# Sheet2.net
KiCad netlist of a schematic drawn in Altium Designer
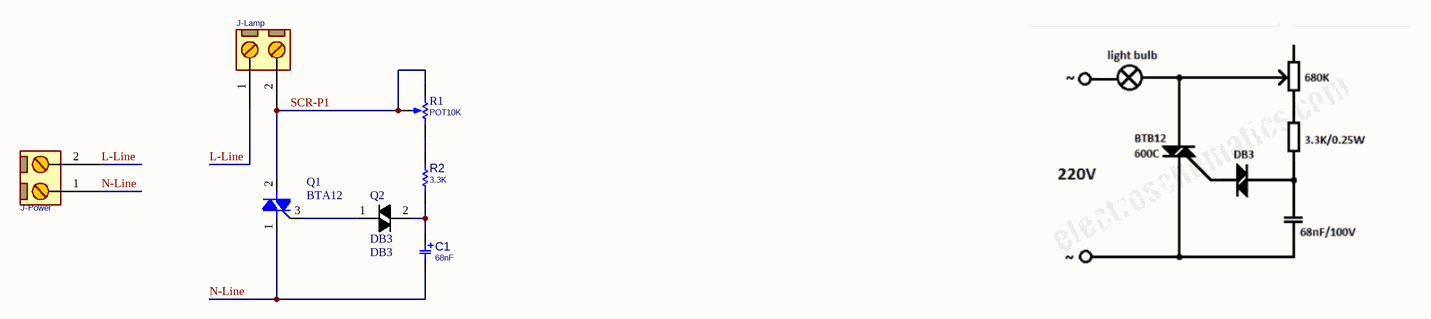
[diagram p0: Sheet2.SchDoc]

(export (version "E")
  (design (tool "Eeschema 10.0.6"))
  (components
    (comp (ref "C1")
      (value "68nF")
      (footprint "C_FLM_7X5H11")
      (description "CAP, THD, FILM,")
      (fields (field (name "MANF_P#") "MANF_PART#") (field (name "MANF") "MANF"))
      (libsource (lib "passive_thd") (part "CAP_THD_FLM"))
    )
    (comp (ref "J-Lamp")
      (value "CONN_TB2")
      (footprint "MSTB_2")
      (description "CONN, PHOENIX MSTB, 5-G, 5.08mm pitch")
      (libsource (lib "") (part "CONN_MSTB_2_1"))
    )
    (comp (ref "J-Power")
      (value "CONN_TB2")
      (footprint "MSTB_2")
      (description "CONN, PHOENIX MSTB, 5-G, 5.08mm pitch")
      (libsource (lib "conn_terminalB") (part "CONN_MSTB_2"))
    )
    (comp (ref "Q1")
      (value "BTA12")
      (footprint "TO220_3")
      (description "Triac, 600V, 12A, TO-220")
      (fields (field (name "MANF_P#") "BTA12-600BW, BTA12-600CW, BTA12-600TW") (field (name "MANF") "ST"))
      (libsource (lib "triac_diac") (part "TRIAC_BTA12-600_TO220"))
    )
    (comp (ref "Q2")
      (value "DB3")
      (footprint "D_AX03_DO35")
      (description "Diac, 32VBO, DO-35")
      (fields (field (name "MANF") "ST") (field (name "ALTIUM_VALUE") "DB3"))
      (libsource (lib "triac_diac") (part "DIAC_DB3_DO35"))
    )
    (comp (ref "R1")
      (value "POT10K")
      (footprint "VOL_R")
      (description "RESISTOR, THD, Potentiometer Volume")
      (libsource (lib "resistor_pot_trimmer") (part "RES_THD_POT_VOL"))
    )
    (comp (ref "R2")
      (value "3.3K")
      (footprint "R025W_AX04")
      (description "RESISTOR, THD")
      (fields (field (name "MANF_P#") "RK73H1ETTP4701F") (field (name "MANF") "KOA SPEER"))
      (libsource (lib "passive_thd") (part "RES_THD"))
    )
  )
  (nets
    (net (code "1") (name "/L-Line") (class "Default")
      (node (ref "J-Lamp") (pin "1") (pinfunction "1_1") (pintype "passive"))
      (node (ref "J-Power") (pin "2") (pinfunction "2_2") (pintype "passive"))
    )
    (net (code "2") (name "/N-Line") (class "Default")
      (node (ref "C1") (pin "2") (pinfunction "2_2") (pintype "passive"))
      (node (ref "J-Power") (pin "1") (pinfunction "1_1") (pintype "passive"))
      (node (ref "Q1") (pin "1") (pinfunction "T1_1") (pintype "passive"))
    )
    (net (code "3") (name "/SCR-P1") (class "Default")
      (node (ref "J-Lamp") (pin "2") (pinfunction "2_2") (pintype "passive"))
      (node (ref "Q1") (pin "2") (pinfunction "T2_2") (pintype "passive"))
      (node (ref "R1") (pin "1") (pinfunction "TOP_1") (pintype "passive"))
      (node (ref "R1") (pin "2") (pinfunction "TAP_2") (pintype "passive"))
    )
    (net (code "4") (name "Net-(Q1-G)") (class "Default")
      (node (ref "Q1") (pin "3") (pinfunction "G_3") (pintype "passive"))
      (node (ref "Q2") (pin "1") (pinfunction "A1_1") (pintype "passive"))
    )
    (net (code "5") (name "Net-(Q2-A2)") (class "Default")
      (node (ref "C1") (pin "1") (pinfunction "1_1") (pintype "passive"))
      (node (ref "Q2") (pin "2") (pinfunction "A2_2") (pintype "passive"))
      (node (ref "R2") (pin "1") (pinfunction "1_1") (pintype "passive"))
    )
    (net (code "6") (name "Net-(R1-BOT)") (class "Default")
      (node (ref "R1") (pin "3") (pinfunction "BOT_3") (pintype "passive"))
      (node (ref "R2") (pin "2") (pinfunction "2_2") (pintype "passive"))
    )
  )
)
